# Sheet3.net
KiCad netlist of a schematic drawn in Altium Designer
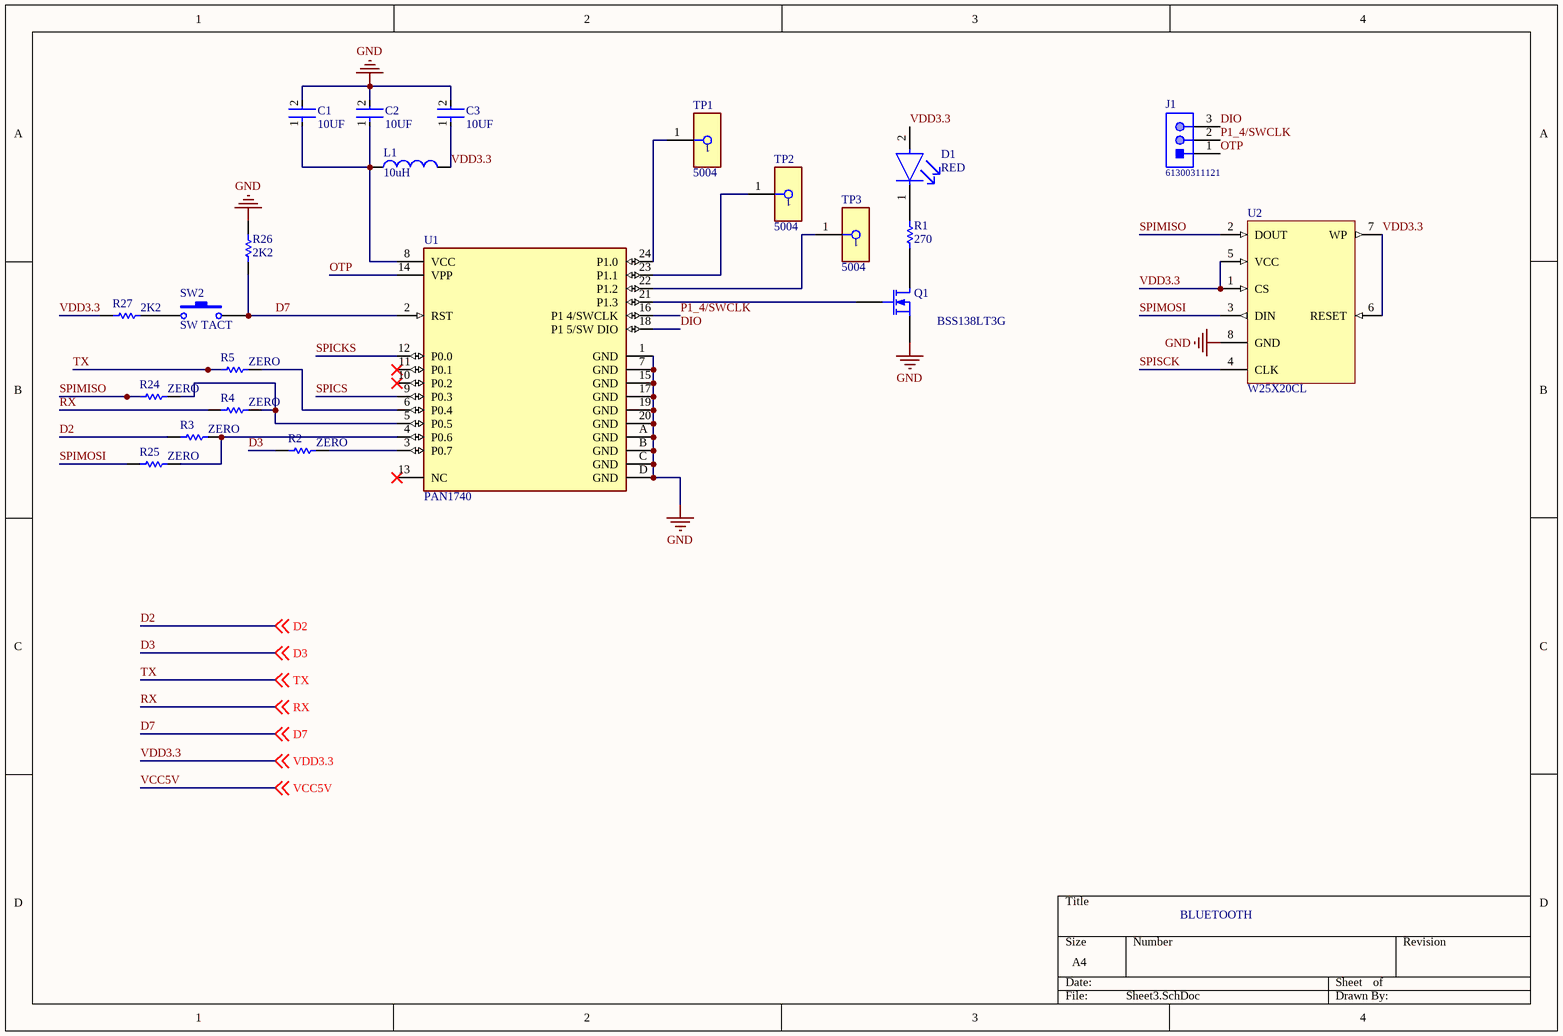
[diagram p0: Sheet3.SchDoc]

(export (version "E")
  (design (tool "Eeschema 10.0.6"))
  (components
    (comp (ref "C1")
      (value "10UF")
      (footprint "FP-C0805C-DN-MFG")
      (description "CAP CER 0.1UF 50V X7R 0805")
      (fields
        (field (name "MANUFACTURER PART NUMBER") "C0805C104K5RACTU")
        (field (name "MANUFACTURER") "KEMET")
      )
      (libsource (lib "Altium Content Vault") (part "b4654b650e69147ec39a6b967a45e02"))
    )
    (comp (ref "C2")
      (value "10UF")
      (footprint "FP-C0805C-DN-MFG")
      (description "CAP CER 0.1UF 50V X7R 0805")
      (fields
        (field (name "MANUFACTURER PART NUMBER") "C0805C104K5RACTU")
        (field (name "MANUFACTURER") "KEMET")
      )
      (libsource (lib "Altium Content Vault") (part "b4654b650e69147ec39a6b967a45e02"))
    )
    (comp (ref "C3")
      (value "10UF")
      (footprint "FP-C0805C-DN-MFG")
      (description "CAP CER 0.1UF 50V X7R 0805")
      (fields
        (field (name "MANUFACTURER PART NUMBER") "C0805C104K5RACTU")
        (field (name "MANUFACTURER") "KEMET")
      )
      (libsource (lib "Altium Content Vault") (part "b4654b650e69147ec39a6b967a45e02"))
    )
    (comp (ref "D1")
      (value "RED")
      (footprint "FP-LTST-C190GKT-MFG")
      (description "LED GREEN CLEAR CHIP SMD")
      (fields (field (name "VOLTAGE") "2V"))
      (libsource (lib "Altium Content Vault") (part "8706943c75ba83719d021d2fdc84c58"))
    )
    (comp (ref "J1")
      (value "61300311121")
      (footprint "61300311121")
      (description "THT Vertical Pin Header WR-PHD, Pitch 2.54 mm, Single Row, 3 pins")
      (fields (field (name "MANUFACTURER") "Wurth Elektronik") (field (name "PUBLISHER") "WurthElektronik"))
      (libsource (lib "Altium Content Vault") (part "WE-CN-1P-M-R3"))
    )
    (comp (ref "L1")
      (value "10uH")
      (footprint "0402-A")
      (description "Inductor")
      (fields (field (name "PUBLISHER") "Altium Limited"))
      (libsource (lib "Miscellaneous Devices") (part "Inductor"))
    )
    (comp (ref "Q1")
      (value "BSS138LT3G")
      (footprint "E3")
      (description "N-Channel MOSFET")
      (fields (field (name "PUBLISHER") "Altium Limited"))
      (libsource (lib "Miscellaneous Devices") (part "MOSFET-N"))
    )
    (comp (ref "R1")
      (value "270")
      (footprint "RESC1005X40X25NL05T10")
      (fields (field (name "MANUFACTURER") "Yageo / Phycomp") (field (name "PART NUMBER") "RC0402JR-070RL"))
      (libsource (lib "Altium Content Vault") (part "RES"))
    )
    (comp (ref "R2")
      (value "ZERO")
      (footprint "RESC1005X40X25NL05T10")
      (fields (field (name "MANUFACTURER") "Yageo / Phycomp") (field (name "PART NUMBER") "RC0402JR-070RL"))
      (libsource (lib "Altium Content Vault") (part "RES"))
    )
    (comp (ref "R3")
      (value "ZERO")
      (footprint "RESC1005X40X25NL05T10")
      (fields (field (name "MANUFACTURER") "Yageo / Phycomp") (field (name "PART NUMBER") "RC0402JR-070RL"))
      (libsource (lib "Altium Content Vault") (part "RES"))
    )
    (comp (ref "R4")
      (value "ZERO")
      (footprint "RESC1005X40X25NL05T10")
      (fields (field (name "MANUFACTURER") "Yageo / Phycomp") (field (name "PART NUMBER") "RC0402JR-070RL"))
      (libsource (lib "Altium Content Vault") (part "RES"))
    )
    (comp (ref "R5")
      (value "ZERO")
      (footprint "RESC1005X40X25NL05T10")
      (fields (field (name "MANUFACTURER") "Yageo / Phycomp") (field (name "PART NUMBER") "RC0402JR-070RL"))
      (libsource (lib "Altium Content Vault") (part "RES"))
    )
    (comp (ref "R24")
      (value "ZERO")
      (footprint "RESC1005X40X25NL05T10")
      (fields (field (name "MANUFACTURER") "Yageo / Phycomp") (field (name "PART NUMBER") "RC0402JR-070RL"))
      (libsource (lib "Altium Content Vault") (part "RES"))
    )
    (comp (ref "R25")
      (value "ZERO")
      (footprint "RESC1005X40X25NL05T10")
      (fields (field (name "MANUFACTURER") "Yageo / Phycomp") (field (name "PART NUMBER") "RC0402JR-070RL"))
      (libsource (lib "Altium Content Vault") (part "RES"))
    )
    (comp (ref "R26")
      (value "2K2")
      (footprint "RESC1005X40X25NL05T10")
      (fields (field (name "MANUFACTURER") "Yageo / Phycomp") (field (name "PART NUMBER") "RC0402JR-070RL"))
      (libsource (lib "Altium Content Vault") (part "RES"))
    )
    (comp (ref "R27")
      (value "2K2")
      (footprint "RESC1005X40X25NL05T10")
      (fields (field (name "MANUFACTURER") "Yageo / Phycomp") (field (name "PART NUMBER") "RC0402JR-070RL"))
      (libsource (lib "Altium Content Vault") (part "RES"))
    )
    (comp (ref "SW2")
      (value "SW TACT")
      (footprint "SPST-2")
      (description "Switch")
      (fields (field (name "PUBLISHER") "Altium Limited"))
      (libsource (lib "Miscellaneous Devices") (part "SW-PB"))
    )
    (comp (ref "TP1")
      (value "5004")
      (footprint "FP-5004-MFG")
      (description "PC TEST POINT MINIATURE YELLOW")
      (fields
        (field (name "MANUFACTURER") "Keystone")
        (field (name "OCTOPART") "https://octopart.com/5004-keystone-28591")
      )
      (libsource (lib "Altium Content Vault") (part "98815daf2f2c152b0c43f5ab9800df6"))
    )
    (comp (ref "TP2")
      (value "5004")
      (footprint "FP-5004-MFG")
      (description "PC TEST POINT MINIATURE YELLOW")
      (fields
        (field (name "MANUFACTURER") "Keystone")
        (field (name "OCTOPART") "https://octopart.com/5004-keystone-28591")
      )
      (libsource (lib "Altium Content Vault") (part "98815daf2f2c152b0c43f5ab9800df6"))
    )
    (comp (ref "TP3")
      (value "5004")
      (footprint "FP-5004-MFG")
      (description "PC TEST POINT MINIATURE YELLOW")
      (fields
        (field (name "MANUFACTURER") "Keystone")
        (field (name "OCTOPART") "https://octopart.com/5004-keystone-28591")
      )
      (libsource (lib "Altium Content Vault") (part "98815daf2f2c152b0c43f5ab9800df6"))
    )
    (comp (ref "U1")
      (value "PAN1740")
      (footprint "FP-ENW-89846A1KF-MFG")
      (description "RF TXRX MOD BLUETOOTH CHIP ANT")
      (fields
        (field (name "MANUFACTURER") "Panasonic")
        (field (name "OCTOPART") "https://octopart.com/enw-89846a1kf-panasonic-38566823")
      )
      (libsource (lib "Altium Content Vault") (part "e19c780454142849fd90e01d0101f89"))
    )
    (comp (ref "U2")
      (value "W25X20CL")
      (footprint "PDIP300-P8")
      (description "Infrared Encoder/Decoder, PDIP, Extended Temperature")
      (libsource (lib "Altium Content Vault") (part "RF-CDC-MCP2122-8"))
    )
  )
  (nets
    (net (code "1") (name "/DIO") (class "Default")
      (node (ref "J1") (pin "3") (pinfunction "3_3") (pintype "passive"))
      (node (ref "U1") (pin "18") (pinfunction "P1_5/SW_DIO_18") (pintype "bidirectional"))
    )
    (net (code "2") (name "/OTP") (class "Default")
      (node (ref "J1") (pin "1") (pinfunction "1_1") (pintype "passive"))
      (node (ref "U1") (pin "14") (pinfunction "VPP_14") (pintype "power_in"))
    )
    (net (code "3") (name "/P1_4{slash}SWCLK") (class "Default")
      (node (ref "J1") (pin "2") (pinfunction "2_2") (pintype "passive"))
      (node (ref "U1") (pin "16") (pinfunction "P1_4/SWCLK_16") (pintype "bidirectional"))
    )
    (net (code "4") (name "/SPICKS") (class "Default")
      (node (ref "U1") (pin "12") (pinfunction "P0.0_12") (pintype "bidirectional"))
    )
    (net (code "5") (name "/SPICS") (class "Default")
      (node (ref "U1") (pin "9") (pinfunction "P0.3_9") (pintype "bidirectional"))
    )
    (net (code "6") (name "/SPIMISO") (class "Default")
      (node (ref "R24") (pin "1") (pinfunction "1_1") (pintype "passive"))
      (node (ref "U2") (pin "2") (pinfunction "DOUT_2") (pintype "input"))
    )
    (net (code "7") (name "/SPIMOSI") (class "Default")
      (node (ref "R25") (pin "1") (pinfunction "1_1") (pintype "passive"))
      (node (ref "U2") (pin "3") (pinfunction "DIN_3") (pintype "output"))
    )
    (net (code "8") (name "/SPISCK") (class "Default")
      (node (ref "U2") (pin "4") (pinfunction "CLK_4") (pintype "power_in"))
    )
    (net (code "9") (name "D2") (class "Default")
      (node (ref "R3") (pin "1") (pinfunction "1_1") (pintype "passive"))
    )
    (net (code "10") (name "D3") (class "Default")
      (node (ref "R2") (pin "1") (pinfunction "1_1") (pintype "passive"))
    )
    (net (code "11") (name "D7") (class "Default")
      (node (ref "R26") (pin "1") (pinfunction "1_1") (pintype "passive"))
      (node (ref "SW2") (pin "2") (pinfunction "2_2") (pintype "passive"))
      (node (ref "U1") (pin "2") (pinfunction "RST_2") (pintype "input"))
    )
    (net (code "12") (name "GND") (class "Default")
      (node (ref "C1") (pin "2") (pinfunction "2_2") (pintype "passive"))
      (node (ref "C2") (pin "2") (pinfunction "2_2") (pintype "passive"))
      (node (ref "C3") (pin "2") (pinfunction "2_2") (pintype "passive"))
      (node (ref "Q1") (pin "3") (pinfunction "S_3") (pintype "passive"))
      (node (ref "R26") (pin "2") (pinfunction "2_2") (pintype "passive"))
      (node (ref "U1") (pin "1") (pinfunction "GND_1") (pintype "power_in"))
      (node (ref "U1") (pin "15") (pinfunction "GND_15") (pintype "power_in"))
      (node (ref "U1") (pin "17") (pinfunction "GND_17") (pintype "power_in"))
      (node (ref "U1") (pin "19") (pinfunction "GND_19") (pintype "power_in"))
      (node (ref "U1") (pin "20") (pinfunction "GND_20") (pintype "power_in"))
      (node (ref "U1") (pin "7") (pinfunction "GND_7") (pintype "power_in"))
      (node (ref "U1") (pin "A") (pinfunction "GND_A") (pintype "power_in"))
      (node (ref "U1") (pin "B") (pinfunction "GND_B") (pintype "power_in"))
      (node (ref "U1") (pin "C") (pinfunction "GND_C") (pintype "power_in"))
      (node (ref "U1") (pin "D") (pinfunction "GND_D") (pintype "power_in"))
      (node (ref "U2") (pin "8") (pinfunction "GND_8") (pintype "power_in"))
    )
    (net (code "13") (name "Net-(D1-C)") (class "Default")
      (node (ref "D1") (pin "1") (pinfunction "C_1") (pintype "passive"))
      (node (ref "R1") (pin "2") (pinfunction "2_2") (pintype "passive"))
    )
    (net (code "14") (name "Net-(Q1-D)") (class "Default")
      (node (ref "Q1") (pin "1") (pinfunction "D_1") (pintype "passive"))
      (node (ref "R1") (pin "1") (pinfunction "1_1") (pintype "passive"))
    )
    (net (code "15") (name "Net-(Q1-G)") (class "Default")
      (node (ref "Q1") (pin "2") (pinfunction "G_2") (pintype "passive"))
      (node (ref "U1") (pin "21") (pinfunction "P1.3_21") (pintype "bidirectional"))
    )
    (net (code "16") (name "Net-(R27-Pad2)") (class "Default")
      (node (ref "R27") (pin "2") (pinfunction "2_2") (pintype "passive"))
      (node (ref "SW2") (pin "1") (pinfunction "1_1") (pintype "passive"))
    )
    (net (code "17") (name "Net-(U1-P0.4)") (class "Default")
      (node (ref "R5") (pin "2") (pinfunction "2_2") (pintype "passive"))
      (node (ref "U1") (pin "6") (pinfunction "P0.4_6") (pintype "bidirectional"))
    )
    (net (code "18") (name "Net-(U1-P0.5)") (class "Default")
      (node (ref "R24") (pin "2") (pinfunction "2_2") (pintype "passive"))
      (node (ref "R4") (pin "2") (pinfunction "2_2") (pintype "passive"))
      (node (ref "U1") (pin "5") (pinfunction "P0.5_5") (pintype "bidirectional"))
    )
    (net (code "19") (name "Net-(U1-P0.6)") (class "Default")
      (node (ref "R25") (pin "2") (pinfunction "2_2") (pintype "passive"))
      (node (ref "R3") (pin "2") (pinfunction "2_2") (pintype "passive"))
      (node (ref "U1") (pin "4") (pinfunction "P0.6_4") (pintype "bidirectional"))
    )
    (net (code "20") (name "Net-(U1-P0.7)") (class "Default")
      (node (ref "R2") (pin "2") (pinfunction "2_2") (pintype "passive"))
      (node (ref "U1") (pin "3") (pinfunction "P0.7_3") (pintype "bidirectional"))
    )
    (net (code "21") (name "Net-(U1-P1.0)") (class "Default")
      (node (ref "TP1") (pin "1") (pinfunction "1_1") (pintype "passive"))
      (node (ref "U1") (pin "24") (pinfunction "P1.0_24") (pintype "bidirectional"))
    )
    (net (code "22") (name "Net-(U1-P1.1)") (class "Default")
      (node (ref "TP2") (pin "1") (pinfunction "1_1") (pintype "passive"))
      (node (ref "U1") (pin "23") (pinfunction "P1.1_23") (pintype "bidirectional"))
    )
    (net (code "23") (name "Net-(U1-P1.2)") (class "Default")
      (node (ref "TP3") (pin "1") (pinfunction "1_1") (pintype "passive"))
      (node (ref "U1") (pin "22") (pinfunction "P1.2_22") (pintype "bidirectional"))
    )
    (net (code "24") (name "Net-(U1-VCC)") (class "Default")
      (node (ref "C1") (pin "1") (pinfunction "1_1") (pintype "passive"))
      (node (ref "C2") (pin "1") (pinfunction "1_1") (pintype "passive"))
      (node (ref "L1") (pin "1") (pinfunction "1_1") (pintype "passive"))
      (node (ref "U1") (pin "8") (pinfunction "VCC_8") (pintype "power_in"))
    )
    (net (code "25") (name "RX") (class "Default")
      (node (ref "R4") (pin "1") (pinfunction "1_1") (pintype "passive"))
    )
    (net (code "26") (name "TX") (class "Default")
      (node (ref "R5") (pin "1") (pinfunction "1_1") (pintype "passive"))
    )
    (net (code "28") (name "VDD3.3") (class "Default")
      (node (ref "C3") (pin "1") (pinfunction "1_1") (pintype "passive"))
      (node (ref "D1") (pin "2") (pinfunction "A_2") (pintype "passive"))
      (node (ref "L1") (pin "2") (pinfunction "2_2") (pintype "passive"))
      (node (ref "R27") (pin "1") (pinfunction "1_1") (pintype "passive"))
      (node (ref "U2") (pin "1") (pinfunction "CS_1") (pintype "input"))
      (node (ref "U2") (pin "5") (pinfunction "VCC_5") (pintype "input"))
      (node (ref "U2") (pin "6") (pinfunction "RESET_6") (pintype "input"))
      (node (ref "U2") (pin "7") (pinfunction "WP_7") (pintype "output"))
    )
    (net (code "29") (name "unconnected-(U1-NC-Pad13)") (class "Default")
      (node (ref "U1") (pin "13") (pinfunction "NC_13") (pintype "passive+no_connect"))
    )
    (net (code "30") (name "unconnected-(U1-P0.1-Pad11)") (class "Default")
      (node (ref "U1") (pin "11") (pinfunction "P0.1_11") (pintype "bidirectional+no_connect"))
    )
    (net (code "31") (name "unconnected-(U1-P0.2-Pad10)") (class "Default")
      (node (ref "U1") (pin "10") (pinfunction "P0.2_10") (pintype "bidirectional+no_connect"))
    )
  )
)
